# boardboard.net
KiCad netlist of a schematic drawn in Altium Designer
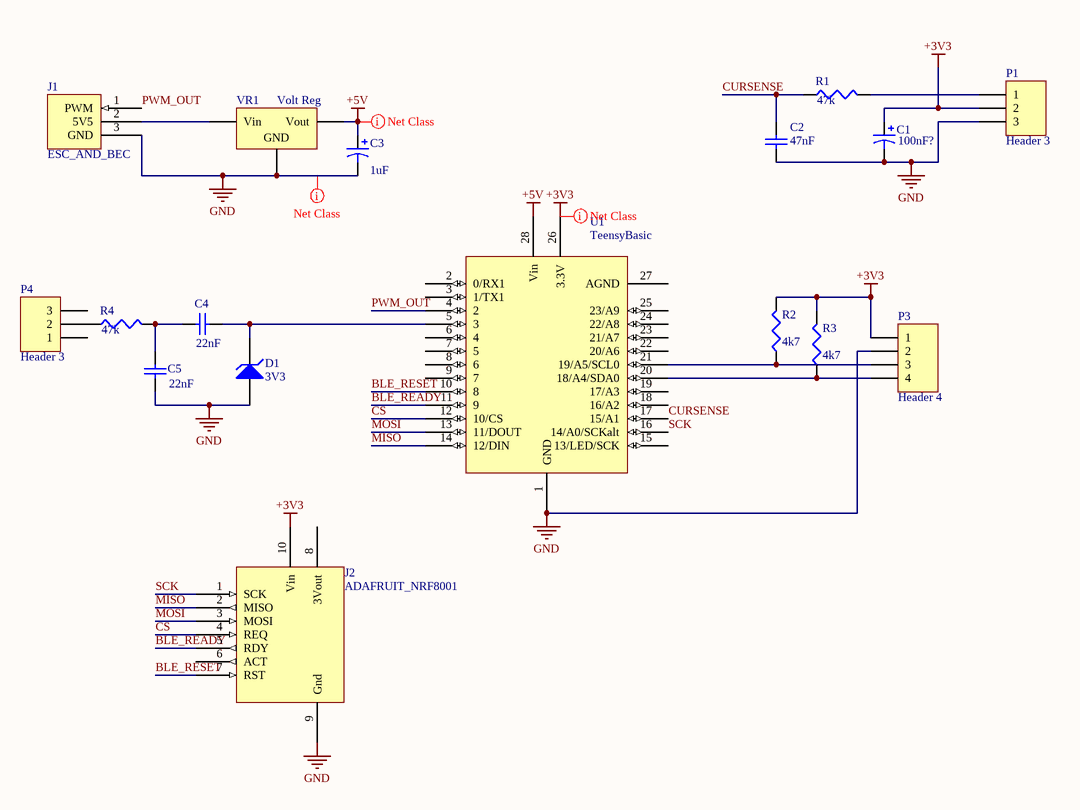
[diagram p0: boardboard.SchDoc]

(export (version "E")
  (design (tool "Eeschema 10.0.6"))
  (components
    (comp (ref "C1")
      (value "100nF?")
      (footprint "C0805")
      (description "Polarized Capacitor (Surface Mount)")
      (fields (field (name "Comment") "Cap Pol3") (field (name "PUBLISHER") "Altium Limited"))
      (libsource (lib "Miscellaneous Devices") (part "Cap Pol3"))
    )
    (comp (ref "C2")
      (value "47nF")
      (footprint "C0805")
      (description "Capacitor")
      (fields (field (name "Comment") "Cap") (field (name "PUBLISHER") "Altium Limited"))
      (libsource (lib "Miscellaneous Devices") (part "Cap"))
    )
    (comp (ref "C3")
      (value "1uF")
      (footprint "C0805")
      (description "Polarized Capacitor (Surface Mount)")
      (fields (field (name "Comment") "Cap Pol3") (field (name "PUBLISHER") "Altium Limited"))
      (libsource (lib "Miscellaneous Devices") (part "Cap Pol3"))
    )
    (comp (ref "C4")
      (value "22nF")
      (footprint "C0805")
      (description "Capacitor")
      (fields (field (name "Comment") "Cap") (field (name "PUBLISHER") "Altium Limited"))
      (libsource (lib "Miscellaneous Devices") (part "Cap"))
    )
    (comp (ref "C5")
      (value "22nF")
      (footprint "C0805")
      (description "Capacitor")
      (fields (field (name "Comment") "Cap") (field (name "PUBLISHER") "Altium Limited"))
      (libsource (lib "Miscellaneous Devices") (part "Cap"))
    )
    (comp (ref "D1")
      (value "3V3")
      (footprint "DO-35")
      (description "Zener Diode")
      (fields (field (name "PUBLISHER") "Altium Limited"))
      (libsource (lib "Miscellaneous Devices") (part "D Zener"))
    )
    (comp (ref "J1")
      (value "ESC_AND_BEC")
      (footprint "HDR1X3H")
      (libsource (lib "Teensy") (part "ESC_AND_BEC"))
    )
    (comp (ref "J2")
      (value "ADAFRUIT_NRF8001")
      (footprint "HDR1X10")
      (libsource (lib "Teensy") (part "ADAFRUIT_NRF8001"))
    )
    (comp (ref "P1")
      (value "Header 3")
      (footprint "HDR1X3H")
      (description "Header, 3-Pin")
      (fields (field (name "PUBLISHER") "Altium Limited"))
      (libsource (lib "Miscellaneous Connectors") (part "Header 3"))
    )
    (comp (ref "P3")
      (value "Header 4")
      (footprint "HDR1x4H")
      (description "Header, 4-Pin")
      (fields (field (name "PUBLISHER") "Altium Limited"))
      (libsource (lib "Miscellaneous Connectors") (part "Header 4"))
    )
    (comp (ref "P4")
      (value "Header 3")
      (footprint "HDR1X3H")
      (description "Header, 3-Pin")
      (fields (field (name "PUBLISHER") "Altium Limited"))
      (libsource (lib "") (part "Header 3_1"))
    )
    (comp (ref "R1")
      (value "47k")
      (footprint "6-0805_N")
      (description "Resistor")
      (fields (field (name "Comment") "Res3") (field (name "PUBLISHER") "Altium Limited"))
      (libsource (lib "Miscellaneous Devices") (part "Res3"))
    )
    (comp (ref "R2")
      (value "4k7")
      (footprint "6-0805_N")
      (description "Resistor")
      (fields (field (name "Comment") "Res3") (field (name "PUBLISHER") "Altium Limited"))
      (libsource (lib "Miscellaneous Devices") (part "Res3"))
    )
    (comp (ref "R3")
      (value "4k7")
      (footprint "6-0805_N")
      (description "Resistor")
      (fields (field (name "Comment") "Res3") (field (name "PUBLISHER") "Altium Limited"))
      (libsource (lib "Miscellaneous Devices") (part "Res3"))
    )
    (comp (ref "R4")
      (value "47k")
      (footprint "6-0805_N")
      (description "Resistor")
      (fields (field (name "Comment") "Res3") (field (name "PUBLISHER") "Altium Limited"))
      (libsource (lib "Miscellaneous Devices") (part "Res3"))
    )
    (comp (ref "U1")
      (value "TeensyBasic")
      (footprint "TeensyBasic")
      (libsource (lib "Teensy") (part "TeensyBasic"))
    )
    (comp (ref "VR1")
      (value "Volt Reg")
      (footprint "SOT223_N")
      (description "Voltage Regulator")
      (fields (field (name "PUBLISHER") "Altium Limited"))
      (libsource (lib "Miscellaneous Devices") (part "Volt Reg"))
    )
  )
  (nets
    (net (code "1") (name "+3V3") (class "Default")
      (node (ref "C1") (pin "1") (pinfunction "1_1") (pintype "passive"))
      (node (ref "J2") (pin "10") (pinfunction "Vin_10") (pintype "power_in"))
      (node (ref "P1") (pin "2") (pinfunction "2_2") (pintype "passive"))
      (node (ref "P3") (pin "1") (pinfunction "1_1") (pintype "passive"))
      (node (ref "R2") (pin "2") (pinfunction "2_2") (pintype "passive"))
      (node (ref "R3") (pin "2") (pinfunction "2_2") (pintype "passive"))
      (node (ref "U1") (pin "26") (pinfunction "3.3V_26") (pintype "power_in"))
    )
    (net (code "2") (name "+5V") (class "Default")
      (node (ref "C3") (pin "1") (pinfunction "1_1") (pintype "passive"))
      (node (ref "U1") (pin "28") (pinfunction "Vin_28") (pintype "power_in"))
      (node (ref "VR1") (pin "3") (pinfunction "Vout_3") (pintype "passive"))
    )
    (net (code "3") (name "/BLE_READY") (class "Default")
      (node (ref "J2") (pin "5") (pinfunction "RDY_5") (pintype "output"))
      (node (ref "U1") (pin "11") (pinfunction "9_11") (pintype "bidirectional"))
    )
    (net (code "4") (name "/BLE_RESET") (class "Default")
      (node (ref "J2") (pin "7") (pinfunction "RST_7") (pintype "input"))
      (node (ref "U1") (pin "10") (pinfunction "8_10") (pintype "bidirectional"))
    )
    (net (code "5") (name "/CS") (class "Default")
      (node (ref "J2") (pin "4") (pinfunction "REQ_4") (pintype "input"))
      (node (ref "U1") (pin "12") (pinfunction "10/CS_12") (pintype "bidirectional"))
    )
    (net (code "6") (name "/CURSENSE") (class "Default")
      (node (ref "C2") (pin "2") (pinfunction "2_2") (pintype "passive"))
      (node (ref "R1") (pin "1") (pinfunction "1_1") (pintype "passive"))
      (node (ref "U1") (pin "17") (pinfunction "15/A1_17") (pintype "bidirectional"))
    )
    (net (code "7") (name "/MISO") (class "Default")
      (node (ref "J2") (pin "2") (pinfunction "MISO_2") (pintype "output"))
      (node (ref "U1") (pin "14") (pinfunction "12/DIN_14") (pintype "bidirectional"))
    )
    (net (code "8") (name "/MOSI") (class "Default")
      (node (ref "J2") (pin "3") (pinfunction "MOSI_3") (pintype "input"))
      (node (ref "U1") (pin "13") (pinfunction "11/DOUT_13") (pintype "bidirectional"))
    )
    (net (code "9") (name "/PWM_OUT") (class "Default")
      (node (ref "J1") (pin "1") (pinfunction "PWM_1") (pintype "input"))
      (node (ref "U1") (pin "4") (pinfunction "2_4") (pintype "bidirectional"))
    )
    (net (code "10") (name "/SCK") (class "Default")
      (node (ref "J2") (pin "1") (pinfunction "SCK_1") (pintype "input"))
      (node (ref "U1") (pin "16") (pinfunction "14/A0/SCKalt_16") (pintype "bidirectional"))
    )
    (net (code "11") (name "GND") (class "Default")
      (node (ref "C1") (pin "2") (pinfunction "2_2") (pintype "passive"))
      (node (ref "C2") (pin "1") (pinfunction "1_1") (pintype "passive"))
      (node (ref "C3") (pin "2") (pinfunction "2_2") (pintype "passive"))
      (node (ref "C5") (pin "1") (pinfunction "1_1") (pintype "passive"))
      (node (ref "D1") (pin "1") (pinfunction "A_1") (pintype "passive"))
      (node (ref "J1") (pin "3") (pinfunction "GND_3") (pintype "power_in"))
      (node (ref "J2") (pin "9") (pinfunction "Gnd_9") (pintype "power_in"))
      (node (ref "P1") (pin "3") (pinfunction "3_3") (pintype "passive"))
      (node (ref "P3") (pin "2") (pinfunction "2_2") (pintype "passive"))
      (node (ref "U1") (pin "1") (pinfunction "GND_1") (pintype "power_in"))
      (node (ref "VR1") (pin "2") (pinfunction "GND_2") (pintype "passive"))
    )
    (net (code "12") (name "Net-(C4-Pad1)") (class "Default")
      (node (ref "C4") (pin "1") (pinfunction "1_1") (pintype "passive"))
      (node (ref "C5") (pin "2") (pinfunction "2_2") (pintype "passive"))
      (node (ref "R4") (pin "2") (pinfunction "2_2") (pintype "passive"))
    )
    (net (code "13") (name "Net-(D1-K)") (class "Default")
      (node (ref "C4") (pin "2") (pinfunction "2_2") (pintype "passive"))
      (node (ref "D1") (pin "2") (pinfunction "K_2") (pintype "passive"))
      (node (ref "U1") (pin "5") (pinfunction "3_5") (pintype "bidirectional"))
    )
    (net (code "14") (name "Net-(J1-5V5)") (class "Default")
      (node (ref "J1") (pin "2") (pinfunction "5V5_2") (pintype "power_in"))
      (node (ref "VR1") (pin "1") (pinfunction "Vin_1") (pintype "passive"))
    )
    (net (code "15") (name "Net-(P1-Pad1)") (class "Default")
      (node (ref "P1") (pin "1") (pinfunction "1_1") (pintype "passive"))
      (node (ref "R1") (pin "2") (pinfunction "2_2") (pintype "passive"))
    )
    (net (code "16") (name "Net-(P4-Pad2)") (class "Default")
      (node (ref "P4") (pin "2") (pinfunction "2_2") (pintype "passive"))
      (node (ref "R4") (pin "1") (pinfunction "1_1") (pintype "passive"))
    )
    (net (code "17") (name "Net-(U1-18{slash}A4{slash}SDA0)") (class "Default")
      (node (ref "P3") (pin "4") (pinfunction "4_4") (pintype "passive"))
      (node (ref "R3") (pin "1") (pinfunction "1_1") (pintype "passive"))
      (node (ref "U1") (pin "20") (pinfunction "18/A4/SDA0_20") (pintype "bidirectional"))
    )
    (net (code "18") (name "Net-(U1-19{slash}A5{slash}SCL0)") (class "Default")
      (node (ref "P3") (pin "3") (pinfunction "3_3") (pintype "passive"))
      (node (ref "R2") (pin "1") (pinfunction "1_1") (pintype "passive"))
      (node (ref "U1") (pin "21") (pinfunction "19/A5/SCL0_21") (pintype "bidirectional"))
    )
    (net (code "19") (name "unconnected-(J2-3Vout-Pad8)") (class "Default")
      (node (ref "J2") (pin "8") (pinfunction "3Vout_8") (pintype "power_in"))
    )
    (net (code "20") (name "unconnected-(J2-ACT-Pad6)") (class "Default")
      (node (ref "J2") (pin "6") (pinfunction "ACT_6") (pintype "output"))
    )
    (net (code "21") (name "unconnected-(P4-Pad1)") (class "Default")
      (node (ref "P4") (pin "1") (pinfunction "1_1") (pintype "passive"))
    )
    (net (code "22") (name "unconnected-(P4-Pad3)") (class "Default")
      (node (ref "P4") (pin "3") (pinfunction "3_3") (pintype "passive"))
    )
    (net (code "23") (name "unconnected-(U1-0{slash}RX1-Pad2)") (class "Default")
      (node (ref "U1") (pin "2") (pinfunction "0/RX1_2") (pintype "bidirectional"))
    )
    (net (code "24") (name "unconnected-(U1-1{slash}TX1-Pad3)") (class "Default")
      (node (ref "U1") (pin "3") (pinfunction "1/TX1_3") (pintype "bidirectional"))
    )
    (net (code "25") (name "unconnected-(U1-4-Pad6)") (class "Default")
      (node (ref "U1") (pin "6") (pinfunction "4_6") (pintype "bidirectional"))
    )
    (net (code "26") (name "unconnected-(U1-5-Pad7)") (class "Default")
      (node (ref "U1") (pin "7") (pinfunction "5_7") (pintype "bidirectional"))
    )
    (net (code "27") (name "unconnected-(U1-6-Pad8)") (class "Default")
      (node (ref "U1") (pin "8") (pinfunction "6_8") (pintype "bidirectional"))
    )
    (net (code "28") (name "unconnected-(U1-7-Pad9)") (class "Default")
      (node (ref "U1") (pin "9") (pinfunction "7_9") (pintype "bidirectional"))
    )
    (net (code "29") (name "unconnected-(U1-13{slash}LED{slash}SCK-Pad15)") (class "Default")
      (node (ref "U1") (pin "15") (pinfunction "13/LED/SCK_15") (pintype "bidirectional"))
    )
    (net (code "30") (name "unconnected-(U1-16{slash}A2-Pad18)") (class "Default")
      (node (ref "U1") (pin "18") (pinfunction "16/A2_18") (pintype "bidirectional"))
    )
    (net (code "31") (name "unconnected-(U1-17{slash}A3-Pad19)") (class "Default")
      (node (ref "U1") (pin "19") (pinfunction "17/A3_19") (pintype "bidirectional"))
    )
    (net (code "32") (name "unconnected-(U1-20{slash}A6-Pad22)") (class "Default")
      (node (ref "U1") (pin "22") (pinfunction "20/A6_22") (pintype "bidirectional"))
    )
    (net (code "33") (name "unconnected-(U1-21{slash}A7-Pad23)") (class "Default")
      (node (ref "U1") (pin "23") (pinfunction "21/A7_23") (pintype "bidirectional"))
    )
    (net (code "34") (name "unconnected-(U1-22{slash}A8-Pad24)") (class "Default")
      (node (ref "U1") (pin "24") (pinfunction "22/A8_24") (pintype "bidirectional"))
    )
    (net (code "35") (name "unconnected-(U1-23{slash}A9-Pad25)") (class "Default")
      (node (ref "U1") (pin "25") (pinfunction "23/A9_25") (pintype "bidirectional"))
    )
    (net (code "36") (name "unconnected-(U1-AGND-Pad27)") (class "Default")
      (node (ref "U1") (pin "27") (pinfunction "AGND_27") (pintype "power_in"))
    )
  )
)
